# BMS-6S-1B_Sch.net
KiCad netlist of a schematic drawn in Altium Designer
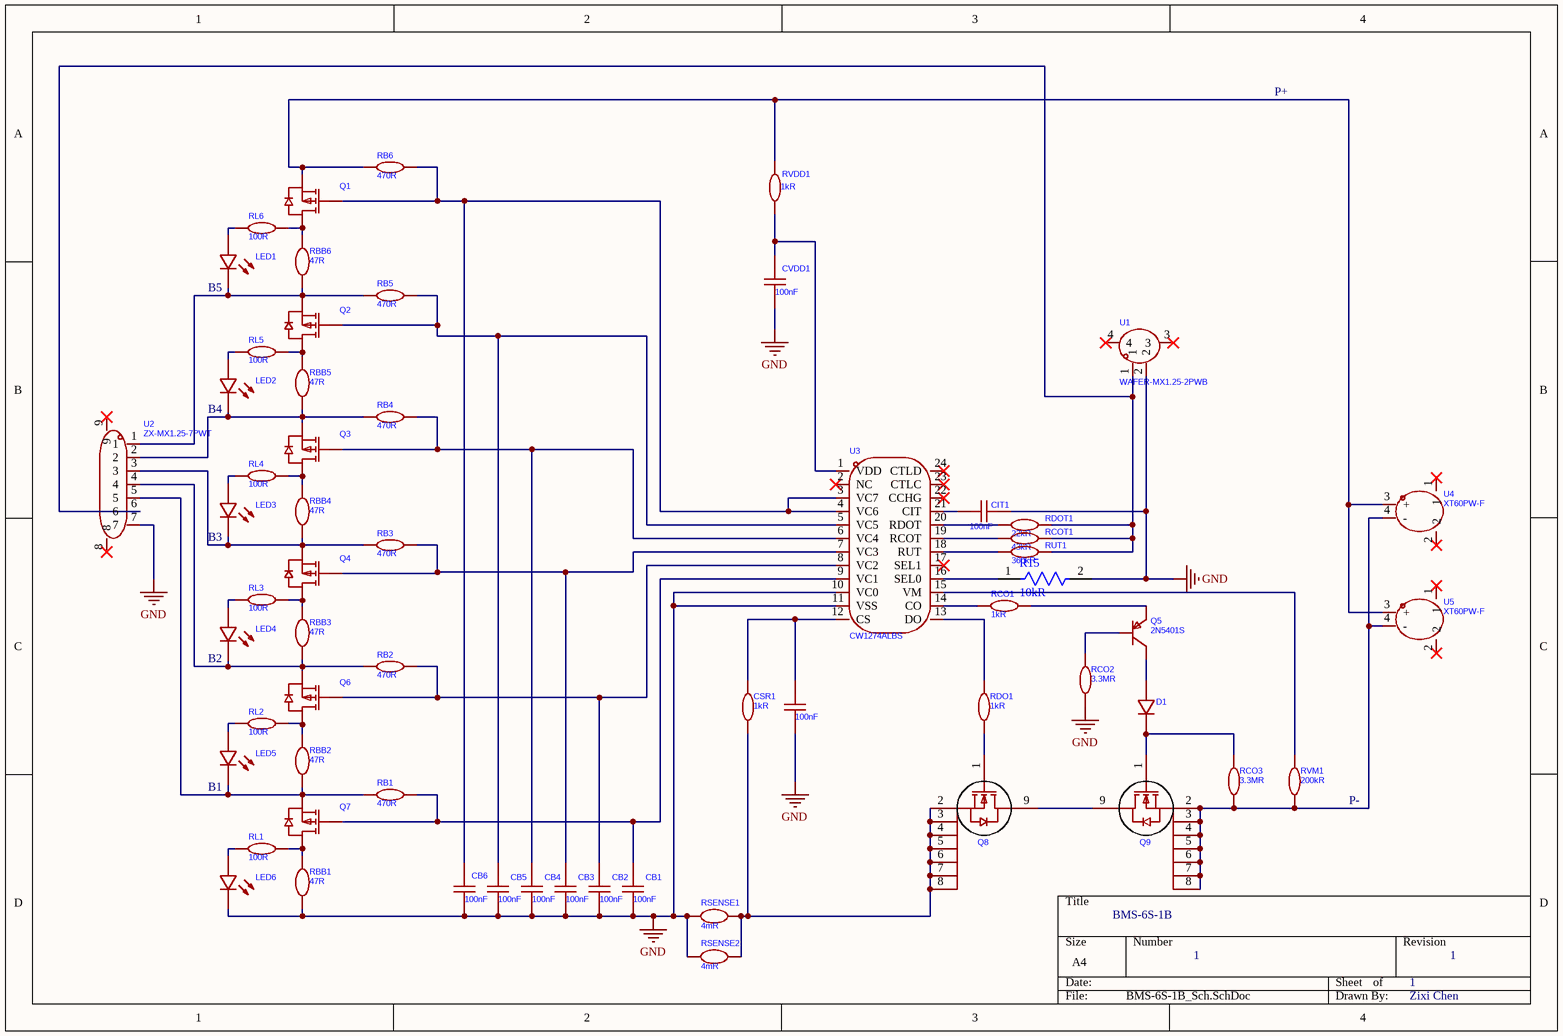
[diagram p0: BMS-6S-1B_Sch.SchDoc]

(export (version "E")
  (design (tool "Eeschema 10.0.6"))
  (components
    (comp (ref "CB1")
      (value "100nF")
      (footprint "C0603")
      (fields
        (field (name "MANUFACTURER") "muRata(村田)")
        (field (name "MANUFACTURER PART") "GCJ188R71H104KA12D")
        (field (name "TOLERANCE") "10%")
      )
      (libsource (lib "Zixi's  personal space") (part "GCJ188R71H104KA12D"))
    )
    (comp (ref "CB2")
      (value "100nF")
      (footprint "C0603")
      (fields
        (field (name "MANUFACTURER") "muRata(村田)")
        (field (name "MANUFACTURER PART") "GCJ188R71H104KA12D")
        (field (name "TOLERANCE") "10%")
      )
      (libsource (lib "Zixi's  personal space") (part "GCJ188R71H104KA12D"))
    )
    (comp (ref "CB3")
      (value "100nF")
      (footprint "C0603")
      (fields
        (field (name "MANUFACTURER") "muRata(村田)")
        (field (name "MANUFACTURER PART") "GCJ188R71H104KA12D")
        (field (name "TOLERANCE") "10%")
      )
      (libsource (lib "Zixi's  personal space") (part "GCJ188R71H104KA12D"))
    )
    (comp (ref "CB4")
      (value "100nF")
      (footprint "C0603")
      (fields
        (field (name "MANUFACTURER") "muRata(村田)")
        (field (name "MANUFACTURER PART") "GCJ188R71H104KA12D")
        (field (name "TOLERANCE") "10%")
      )
      (libsource (lib "Zixi's  personal space") (part "GCJ188R71H104KA12D"))
    )
    (comp (ref "CB5")
      (value "100nF")
      (footprint "C0603")
      (fields
        (field (name "MANUFACTURER") "muRata(村田)")
        (field (name "MANUFACTURER PART") "GCJ188R71H104KA12D")
        (field (name "TOLERANCE") "10%")
      )
      (libsource (lib "Zixi's  personal space") (part "GCJ188R71H104KA12D"))
    )
    (comp (ref "CB6")
      (value "100nF")
      (footprint "C0603")
      (fields
        (field (name "MANUFACTURER") "muRata(村田)")
        (field (name "MANUFACTURER PART") "GCJ188R71H104KA12D")
        (field (name "TOLERANCE") "10%")
      )
      (libsource (lib "Zixi's  personal space") (part "GCJ188R71H104KA12D"))
    )
    (comp (ref "CIT1")
      (value "100nF")
      (footprint "C0603")
      (fields
        (field (name "MANUFACTURER") "muRata(村田)")
        (field (name "MANUFACTURER PART") "GCJ188R71H104KA12D")
        (field (name "TOLERANCE") "10%")
      )
      (libsource (lib "Zixi's  personal space") (part "GCJ188R71H104KA12D"))
    )
    (comp (ref "CSC1")
      (value "100nF")
      (footprint "C0603")
      (fields
        (field (name "MANUFACTURER") "muRata(村田)")
        (field (name "MANUFACTURER PART") "GCJ188R71H104KA12D")
        (field (name "TOLERANCE") "10%")
      )
      (libsource (lib "Zixi's  personal space") (part "GCJ188R71H104KA12D"))
    )
    (comp (ref "CSR1")
      (value "1kR")
      (footprint "R0603")
      (fields
        (field (name "MANUFACTURER") "UNI-ROYAL(厚声)")
        (field (name "TOLERANCE") "1%")
        (field (name "MANUFACTURER PART") "0603WAF1001T5E")
      )
      (libsource (lib "Zixi's  personal space") (part "RC0603FR-07100RL"))
    )
    (comp (ref "CVDD1")
      (value "100nF")
      (footprint "C0603")
      (fields
        (field (name "MANUFACTURER") "muRata(村田)")
        (field (name "MANUFACTURER PART") "GCJ188R71H104KA12D")
        (field (name "TOLERANCE") "10%")
      )
      (libsource (lib "Zixi's  personal space") (part "GCJ188R71H104KA12D"))
    )
    (comp (ref "D1")
      (value "1SS355_C8485")
      (footprint "SOD-323_L1.8-W1.3-LS2.5-RD")
      (fields (field (name "MANUFACTURER") "CJ(江苏长电/长晶)") (field (name "MANUFACTURER PART") "1SS355"))
      (libsource (lib "Zixi's  personal space") (part "1SS355_C8485"))
    )
    (comp (ref "LED1")
      (value "NCD0603O1")
      (footprint "LED0603-RD")
      (fields (field (name "MANUFACTURER") "国星光电"))
      (libsource (lib "Zixi's  personal space") (part "NCD0603O1"))
    )
    (comp (ref "LED2")
      (value "NCD0603O1")
      (footprint "LED0603-RD")
      (fields (field (name "MANUFACTURER") "国星光电"))
      (libsource (lib "Zixi's  personal space") (part "NCD0603O1"))
    )
    (comp (ref "LED3")
      (value "NCD0603O1")
      (footprint "LED0603-RD")
      (fields (field (name "MANUFACTURER") "国星光电"))
      (libsource (lib "Zixi's  personal space") (part "NCD0603O1"))
    )
    (comp (ref "LED4")
      (value "NCD0603O1")
      (footprint "LED0603-RD")
      (fields (field (name "MANUFACTURER") "国星光电"))
      (libsource (lib "Zixi's  personal space") (part "NCD0603O1"))
    )
    (comp (ref "LED5")
      (value "NCD0603O1")
      (footprint "LED0603-RD")
      (fields (field (name "MANUFACTURER") "国星光电"))
      (libsource (lib "Zixi's  personal space") (part "NCD0603O1"))
    )
    (comp (ref "LED6")
      (value "NCD0603O1")
      (footprint "LED0603-RD")
      (fields (field (name "MANUFACTURER") "国星光电"))
      (libsource (lib "Zixi's  personal space") (part "NCD0603O1"))
    )
    (comp (ref "Q1")
      (value "AO3401A_C15127")
      (footprint "SOT-23_L2.9-W1.3-P1.90-LS2.4-BR")
      (fields (field (name "MANUFACTURER PART") "AO3401A") (field (name "MANUFACTURER") "AOS"))
      (libsource (lib "Zixi's  personal space") (part "AO3401A_C15127"))
    )
    (comp (ref "Q2")
      (value "AO3401A_C15127")
      (footprint "SOT-23_L2.9-W1.3-P1.90-LS2.4-BR")
      (fields (field (name "MANUFACTURER PART") "AO3401A") (field (name "MANUFACTURER") "AOS"))
      (libsource (lib "Zixi's  personal space") (part "AO3401A_C15127"))
    )
    (comp (ref "Q3")
      (value "AO3401A_C15127")
      (footprint "SOT-23_L2.9-W1.3-P1.90-LS2.4-BR")
      (fields (field (name "MANUFACTURER PART") "AO3401A") (field (name "MANUFACTURER") "AOS"))
      (libsource (lib "Zixi's  personal space") (part "AO3401A_C15127"))
    )
    (comp (ref "Q4")
      (value "AO3401A_C15127")
      (footprint "SOT-23_L2.9-W1.3-P1.90-LS2.4-BR")
      (fields (field (name "MANUFACTURER PART") "AO3401A") (field (name "MANUFACTURER") "AOS"))
      (libsource (lib "Zixi's  personal space") (part "AO3401A_C15127"))
    )
    (comp (ref "Q5")
      (value "2N5401S")
      (footprint "SOT-23-3_L2.9-W1.5-P2.0-LS2.5-BR")
      (fields (field (name "MANUFACTURER") "TECH PUBLIC(台舟)"))
      (libsource (lib "Zixi's  personal space") (part "2N5401S"))
    )
    (comp (ref "Q6")
      (value "AO3401A_C15127")
      (footprint "SOT-23_L2.9-W1.3-P1.90-LS2.4-BR")
      (fields (field (name "MANUFACTURER PART") "AO3401A") (field (name "MANUFACTURER") "AOS"))
      (libsource (lib "Zixi's  personal space") (part "AO3401A_C15127"))
    )
    (comp (ref "Q7")
      (value "AO3401A_C15127")
      (footprint "SOT-23_L2.9-W1.3-P1.90-LS2.4-BR")
      (fields (field (name "MANUFACTURER PART") "AO3401A") (field (name "MANUFACTURER") "AOS"))
      (libsource (lib "Zixi's  personal space") (part "AO3401A_C15127"))
    )
    (comp (ref "Q8")
      (value "IPLU250N04S4-1R7")
      (footprint "PG-HSOF-8_L10.5-W10.1-P1.20-LS11.9-TL")
      (fields (field (name "MANUFACTURER") "Infineon(英飞凌)"))
      (libsource (lib "Zixi's  personal space") (part "IPLU250N04S4-1R7"))
    )
    (comp (ref "Q9")
      (value "IPLU250N04S4-1R7")
      (footprint "PG-HSOF-8_L10.5-W10.1-P1.20-LS11.9-TL")
      (fields (field (name "MANUFACTURER") "Infineon(英飞凌)"))
      (libsource (lib "Zixi's  personal space") (part "IPLU250N04S4-1R7"))
    )
    (comp (ref "R15")
      (value "10kR")
      (footprint "FP-ESR10-IPC_C")
      (description "10kΩ ±0.5% 0.4W 0805 Anti-Surge Chip Resistor AEC-Q200")
      (libsource (lib "Altium Content Vault") (part "1029c3af85768c4190bb7ad29bc67b5"))
    )
    (comp (ref "RB1")
      (value "470R")
      (footprint "R0603")
      (fields
        (field (name "MANUFACTURER") "UNI-ROYAL(厚声)")
        (field (name "MANUFACTURER PART") "0603WAF4700T5E")
        (field (name "TOLERANCE") "1%")
      )
      (libsource (lib "Zixi's  personal space") (part "RC0603FR-07100RL"))
    )
    (comp (ref "RB2")
      (value "470R")
      (footprint "R0603")
      (fields
        (field (name "MANUFACTURER") "UNI-ROYAL(厚声)")
        (field (name "MANUFACTURER PART") "0603WAF4700T5E")
        (field (name "TOLERANCE") "1%")
      )
      (libsource (lib "Zixi's  personal space") (part "RC0603FR-07100RL"))
    )
    (comp (ref "RB3")
      (value "470R")
      (footprint "R0603")
      (fields
        (field (name "MANUFACTURER") "UNI-ROYAL(厚声)")
        (field (name "MANUFACTURER PART") "0603WAF4700T5E")
        (field (name "TOLERANCE") "1%")
      )
      (libsource (lib "Zixi's  personal space") (part "RC0603FR-07100RL"))
    )
    (comp (ref "RB4")
      (value "470R")
      (footprint "R0603")
      (fields
        (field (name "MANUFACTURER") "UNI-ROYAL(厚声)")
        (field (name "MANUFACTURER PART") "0603WAF4700T5E")
        (field (name "TOLERANCE") "1%")
      )
      (libsource (lib "Zixi's  personal space") (part "RC0603FR-07100RL"))
    )
    (comp (ref "RB5")
      (value "470R")
      (footprint "R0603")
      (fields
        (field (name "MANUFACTURER") "UNI-ROYAL(厚声)")
        (field (name "MANUFACTURER PART") "0603WAF4700T5E")
        (field (name "TOLERANCE") "1%")
      )
      (libsource (lib "Zixi's  personal space") (part "RC0603FR-07100RL"))
    )
    (comp (ref "RB6")
      (value "470R")
      (footprint "R0603")
      (fields
        (field (name "MANUFACTURER") "UNI-ROYAL(厚声)")
        (field (name "MANUFACTURER PART") "0603WAF4700T5E")
        (field (name "TOLERANCE") "1%")
      )
      (libsource (lib "Zixi's  personal space") (part "RC0603FR-07100RL"))
    )
    (comp (ref "RBB1")
      (value "47R")
      (footprint "R2512")
      (fields
        (field (name "TOLERANCE") "1%")
        (field (name "MANUFACTURER") "FH(风华)")
        (field (name "MANUFACTURER PART") "RC-12K47R0FT")
      )
      (libsource (lib "Zixi's  personal space") (part "HolRS3920-3W-4mR-1"))
    )
    (comp (ref "RBB2")
      (value "47R")
      (footprint "R2512")
      (fields
        (field (name "TOLERANCE") "1%")
        (field (name "MANUFACTURER") "FH(风华)")
        (field (name "MANUFACTURER PART") "RC-12K47R0FT")
      )
      (libsource (lib "Zixi's  personal space") (part "HolRS3920-3W-4mR-1"))
    )
    (comp (ref "RBB3")
      (value "47R")
      (footprint "R2512")
      (fields
        (field (name "TOLERANCE") "1%")
        (field (name "MANUFACTURER") "FH(风华)")
        (field (name "MANUFACTURER PART") "RC-12K47R0FT")
      )
      (libsource (lib "Zixi's  personal space") (part "HolRS3920-3W-4mR-1"))
    )
    (comp (ref "RBB4")
      (value "47R")
      (footprint "R2512")
      (fields
        (field (name "TOLERANCE") "1%")
        (field (name "MANUFACTURER") "FH(风华)")
        (field (name "MANUFACTURER PART") "RC-12K47R0FT")
      )
      (libsource (lib "Zixi's  personal space") (part "HolRS3920-3W-4mR-1"))
    )
    (comp (ref "RBB5")
      (value "47R")
      (footprint "R2512")
      (fields
        (field (name "TOLERANCE") "1%")
        (field (name "MANUFACTURER") "FH(风华)")
        (field (name "MANUFACTURER PART") "RC-12K47R0FT")
      )
      (libsource (lib "Zixi's  personal space") (part "HolRS3920-3W-4mR-1"))
    )
    (comp (ref "RBB6")
      (value "47R")
      (footprint "R2512")
      (fields
        (field (name "TOLERANCE") "1%")
        (field (name "MANUFACTURER") "FH(风华)")
        (field (name "MANUFACTURER PART") "RC-12K47R0FT")
      )
      (libsource (lib "Zixi's  personal space") (part "HolRS3920-3W-4mR-1"))
    )
    (comp (ref "RCO1")
      (value "1kR")
      (footprint "R0603")
      (fields
        (field (name "MANUFACTURER PART") "0603WAF1001T5E")
        (field (name "MANUFACTURER") "UNI-ROYAL(厚声)")
        (field (name "TOLERANCE") "1%")
      )
      (libsource (lib "Zixi's  personal space") (part "RC0603FR-07100RL"))
    )
    (comp (ref "RCO2")
      (value "3.3MR")
      (footprint "R0603")
      (fields
        (field (name "MANUFACTURER PART") "0603WAF3304T5E")
        (field (name "MANUFACTURER") "UNI-ROYAL(厚声)")
        (field (name "TOLERANCE") "1%")
      )
      (libsource (lib "Zixi's  personal space") (part "RC0603FR-07100RL"))
    )
    (comp (ref "RCO3")
      (value "3.3MR")
      (footprint "R0603")
      (fields
        (field (name "MANUFACTURER PART") "0603WAF3304T5E")
        (field (name "MANUFACTURER") "UNI-ROYAL(厚声)")
        (field (name "TOLERANCE") "1%")
      )
      (libsource (lib "Zixi's  personal space") (part "RC0603FR-07100RL"))
    )
    (comp (ref "RCOT1")
      (value "43kR")
      (footprint "R0603")
      (fields
        (field (name "MANUFACTURER") "UNI-ROYAL(厚声)")
        (field (name "TOLERANCE") "1%")
        (field (name "MANUFACTURER PART") "0603WAF4302T5E")
      )
      (libsource (lib "Zixi's  personal space") (part "RC0603FR-07100RL"))
    )
    (comp (ref "RDO1")
      (value "1kR")
      (footprint "R0603")
      (fields
        (field (name "MANUFACTURER PART") "0603WAF1001T5E")
        (field (name "MANUFACTURER") "UNI-ROYAL(厚声)")
        (field (name "TOLERANCE") "1%")
      )
      (libsource (lib "Zixi's  personal space") (part "RC0603FR-07100RL"))
    )
    (comp (ref "RDOT1")
      (value "22kR")
      (footprint "R0603")
      (fields
        (field (name "TOLERANCE") "1%")
        (field (name "MANUFACTURER PART") "0603WAF2202T5E")
        (field (name "MANUFACTURER") "UNI-ROYAL(厚声)")
      )
      (libsource (lib "Zixi's  personal space") (part "RC0603FR-07100RL"))
    )
    (comp (ref "RL1")
      (value "100R")
      (footprint "R0603")
      (fields
        (field (name "MANUFACTURER PART") "RC0603FR-07100RL")
        (field (name "TOLERANCE") "1%")
        (field (name "MANUFACTURER") "YAGEO(国巨)")
      )
      (libsource (lib "Zixi's  personal space") (part "RC0603FR-07100RL"))
    )
    (comp (ref "RL2")
      (value "100R")
      (footprint "R0603")
      (fields
        (field (name "MANUFACTURER PART") "RC0603FR-07100RL")
        (field (name "TOLERANCE") "1%")
        (field (name "MANUFACTURER") "YAGEO(国巨)")
      )
      (libsource (lib "Zixi's  personal space") (part "RC0603FR-07100RL"))
    )
    (comp (ref "RL3")
      (value "100R")
      (footprint "R0603")
      (fields
        (field (name "MANUFACTURER PART") "RC0603FR-07100RL")
        (field (name "TOLERANCE") "1%")
        (field (name "MANUFACTURER") "YAGEO(国巨)")
      )
      (libsource (lib "Zixi's  personal space") (part "RC0603FR-07100RL"))
    )
    (comp (ref "RL4")
      (value "100R")
      (footprint "R0603")
      (fields
        (field (name "MANUFACTURER PART") "RC0603FR-07100RL")
        (field (name "TOLERANCE") "1%")
        (field (name "MANUFACTURER") "YAGEO(国巨)")
      )
      (libsource (lib "Zixi's  personal space") (part "RC0603FR-07100RL"))
    )
    (comp (ref "RL5")
      (value "100R")
      (footprint "R0603")
      (fields
        (field (name "MANUFACTURER PART") "RC0603FR-07100RL")
        (field (name "TOLERANCE") "1%")
        (field (name "MANUFACTURER") "YAGEO(国巨)")
      )
      (libsource (lib "Zixi's  personal space") (part "RC0603FR-07100RL"))
    )
    (comp (ref "RL6")
      (value "100R")
      (footprint "R0603")
      (fields
        (field (name "MANUFACTURER PART") "RC0603FR-07100RL")
        (field (name "TOLERANCE") "1%")
        (field (name "MANUFACTURER") "YAGEO(国巨)")
      )
      (libsource (lib "Zixi's  personal space") (part "RC0603FR-07100RL"))
    )
    (comp (ref "RSENSE1")
      (value "4mR")
      (footprint "R3920")
      (fields
        (field (name "MANUFACTURER PART") "HolRS3920-3W-4mR-1%")
        (field (name "MANUFACTURER") "Milliohm(毫欧)")
        (field (name "TOLERANCE") "1%")
      )
      (libsource (lib "Zixi's  personal space") (part "HolRS3920-3W-4mR-1"))
    )
    (comp (ref "RSENSE2")
      (value "4mR")
      (footprint "R3920")
      (fields
        (field (name "MANUFACTURER PART") "HolRS3920-3W-4mR-1%")
        (field (name "MANUFACTURER") "Milliohm(毫欧)")
        (field (name "TOLERANCE") "1%")
      )
      (libsource (lib "Zixi's  personal space") (part "HolRS3920-3W-4mR-1"))
    )
    (comp (ref "RUT1")
      (value "360kR")
      (footprint "R0603")
      (fields
        (field (name "MANUFACTURER PART") "0603WAF3603T5E")
        (field (name "TOLERANCE") "1%")
        (field (name "MANUFACTURER") "UNI-ROYAL(厚声)")
      )
      (libsource (lib "Zixi's  personal space") (part "RC0603FR-07100RL"))
    )
    (comp (ref "RVDD1")
      (value "1kR")
      (footprint "R0603")
      (fields
        (field (name "MANUFACTURER") "UNI-ROYAL(厚声)")
        (field (name "TOLERANCE") "1%")
        (field (name "MANUFACTURER PART") "0603WAF1001T5E")
      )
      (libsource (lib "Zixi's  personal space") (part "RC0603FR-07100RL"))
    )
    (comp (ref "RVM1")
      (value "200kR")
      (footprint "R0603")
      (fields
        (field (name "MANUFACTURER PART") "0603WAF2003T5E")
        (field (name "MANUFACTURER") "UNI-ROYAL(厚声)")
        (field (name "TOLERANCE") "1%")
      )
      (libsource (lib "Zixi's  personal space") (part "RC0603FR-07100RL"))
    )
    (comp (ref "U1")
      (value "WAFER-MX1.25-2PWB")
      (footprint "CONN-SMD_2P-P1.25_XUNPU_WAFER-MX1.25-2PWB")
      (fields (field (name "MANUFACTURER") "XUNPU(讯普)"))
      (libsource (lib "Zixi's  personal space") (part "WAFER-MX1.25-2PWB"))
    )
    (comp (ref "U2")
      (value "ZX-MX1.25-7PWT")
      (footprint "CONN-SMD_7P-P1.25_ZX-MX1.25-7PWT")
      (fields (field (name "MANUFACTURER") "Megastar(兆星)"))
      (libsource (lib "Zixi's  personal space") (part "ZX-MX1.25-7PWT"))
    )
    (comp (ref "U3")
      (value "CW1274ALBS")
      (footprint "SSOP-24_L8.7-W3.9-P0.64-LS6.0-BL")
      (libsource (lib "Zixi's  personal space") (part "CW1274ALBS"))
    )
    (comp (ref "U4")
      (value "XT60PW-F")
      (footprint "TH_2P-XT60PW-F")
      (fields (field (name "MANUFACTURER") "AMASS(艾迈斯)"))
      (libsource (lib "Zixi's  personal space") (part "XT60PW-F"))
    )
    (comp (ref "U5")
      (value "XT60PW-F")
      (footprint "TH_2P-XT60PW-F")
      (fields (field (name "MANUFACTURER") "AMASS(艾迈斯)"))
      (libsource (lib "Zixi's  personal space") (part "XT60PW-F"))
    )
  )
  (nets
    (net (code "1") (name "GND") (class "Default")
      (node (ref "CB1") (pin "1") (pinfunction "1_1") (pintype "passive"))
      (node (ref "CB2") (pin "1") (pinfunction "1_1") (pintype "passive"))
      (node (ref "CB3") (pin "1") (pinfunction "1_1") (pintype "passive"))
      (node (ref "CB4") (pin "1") (pinfunction "1_1") (pintype "passive"))
      (node (ref "CB5") (pin "1") (pinfunction "1_1") (pintype "passive"))
      (node (ref "CB6") (pin "1") (pinfunction "1_1") (pintype "passive"))
      (node (ref "CIT1") (pin "1") (pinfunction "1_1") (pintype "passive"))
      (node (ref "CSC1") (pin "1") (pinfunction "1_1") (pintype "passive"))
      (node (ref "CVDD1") (pin "1") (pinfunction "1_1") (pintype "passive"))
      (node (ref "LED6") (pin "1") (pinfunction "K_1") (pintype "passive"))
      (node (ref "R15") (pin "2") (pinfunction "2_2") (pintype "passive"))
      (node (ref "RBB1") (pin "1") (pinfunction "1_1") (pintype "passive"))
      (node (ref "RCO2") (pin "1") (pinfunction "1_1") (pintype "passive"))
      (node (ref "RSENSE1") (pin "1") (pinfunction "1_1") (pintype "passive"))
      (node (ref "RSENSE2") (pin "1") (pinfunction "1_1") (pintype "passive"))
      (node (ref "U1") (pin "2") (pinfunction "2_2") (pintype "passive"))
      (node (ref "U2") (pin "7") (pinfunction "7_7") (pintype "passive"))
      (node (ref "U3") (pin "10") (pinfunction "VC0_10") (pintype "passive"))
      (node (ref "U3") (pin "11") (pinfunction "VSS_11") (pintype "passive"))
    )
    (net (code "2") (name "Net-(CSR1-Pad1)") (class "Default")
      (node (ref "CSR1") (pin "1") (pinfunction "1_1") (pintype "passive"))
      (node (ref "Q8") (pin "2") (pinfunction "S_2") (pintype "passive"))
      (node (ref "Q8") (pin "3") (pinfunction "S_3") (pintype "passive"))
      (node (ref "Q8") (pin "4") (pinfunction "S_4") (pintype "passive"))
      (node (ref "Q8") (pin "5") (pinfunction "S_5") (pintype "passive"))
      (node (ref "Q8") (pin "6") (pinfunction "S_6") (pintype "passive"))
      (node (ref "Q8") (pin "7") (pinfunction "S_7") (pintype "passive"))
      (node (ref "Q8") (pin "8") (pinfunction "S_8") (pintype "passive"))
      (node (ref "RSENSE1") (pin "2") (pinfunction "2_2") (pintype "passive"))
      (node (ref "RSENSE2") (pin "2") (pinfunction "2_2") (pintype "passive"))
    )
    (net (code "3") (name "Net-(D1-A)") (class "Default")
      (node (ref "D1") (pin "2") (pinfunction "A_2") (pintype "passive"))
      (node (ref "Q5") (pin "3") (pinfunction "C_3") (pintype "passive"))
    )
    (net (code "4") (name "Net-(D1-K)") (class "Default")
      (node (ref "D1") (pin "1") (pinfunction "K_1") (pintype "passive"))
      (node (ref "Q9") (pin "1") (pinfunction "G_1") (pintype "passive"))
      (node (ref "RCO3") (pin "2") (pinfunction "2_2") (pintype "passive"))
    )
    (net (code "5") (name "Net-(LED1-A)") (class "Default")
      (node (ref "LED1") (pin "2") (pinfunction "A_2") (pintype "passive"))
      (node (ref "RL6") (pin "1") (pinfunction "1_1") (pintype "passive"))
    )
    (net (code "6") (name "Net-(LED1-K)") (class "Default")
      (node (ref "LED1") (pin "1") (pinfunction "K_1") (pintype "passive"))
      (node (ref "Q2") (pin "2") (pinfunction "S_2") (pintype "passive"))
      (node (ref "RB5") (pin "1") (pinfunction "1_1") (pintype "passive"))
      (node (ref "RBB6") (pin "1") (pinfunction "1_1") (pintype "passive"))
      (node (ref "U2") (pin "1") (pinfunction "1_1") (pintype "passive"))
    )
    (net (code "7") (name "Net-(LED2-A)") (class "Default")
      (node (ref "LED2") (pin "2") (pinfunction "A_2") (pintype "passive"))
      (node (ref "RL5") (pin "1") (pinfunction "1_1") (pintype "passive"))
    )
    (net (code "8") (name "Net-(LED2-K)") (class "Default")
      (node (ref "LED2") (pin "1") (pinfunction "K_1") (pintype "passive"))
      (node (ref "Q3") (pin "2") (pinfunction "S_2") (pintype "passive"))
      (node (ref "RB4") (pin "1") (pinfunction "1_1") (pintype "passive"))
      (node (ref "RBB5") (pin "1") (pinfunction "1_1") (pintype "passive"))
      (node (ref "U2") (pin "2") (pinfunction "2_2") (pintype "passive"))
    )
    (net (code "9") (name "Net-(LED3-A)") (class "Default")
      (node (ref "LED3") (pin "2") (pinfunction "A_2") (pintype "passive"))
      (node (ref "RL4") (pin "1") (pinfunction "1_1") (pintype "passive"))
    )
    (net (code "10") (name "Net-(LED3-K)") (class "Default")
      (node (ref "LED3") (pin "1") (pinfunction "K_1") (pintype "passive"))
      (node (ref "Q4") (pin "2") (pinfunction "S_2") (pintype "passive"))
      (node (ref "RB3") (pin "1") (pinfunction "1_1") (pintype "passive"))
      (node (ref "RBB4") (pin "1") (pinfunction "1_1") (pintype "passive"))
      (node (ref "U2") (pin "3") (pinfunction "3_3") (pintype "passive"))
    )
    (net (code "11") (name "Net-(LED4-A)") (class "Default")
      (node (ref "LED4") (pin "2") (pinfunction "A_2") (pintype "passive"))
      (node (ref "RL3") (pin "1") (pinfunction "1_1") (pintype "passive"))
    )
    (net (code "12") (name "Net-(LED4-K)") (class "Default")
      (node (ref "LED4") (pin "1") (pinfunction "K_1") (pintype "passive"))
      (node (ref "Q6") (pin "2") (pinfunction "S_2") (pintype "passive"))
      (node (ref "RB2") (pin "1") (pinfunction "1_1") (pintype "passive"))
      (node (ref "RBB3") (pin "1") (pinfunction "1_1") (pintype "passive"))
      (node (ref "U2") (pin "4") (pinfunction "4_4") (pintype "passive"))
    )
    (net (code "13") (name "Net-(LED5-A)") (class "Default")
      (node (ref "LED5") (pin "2") (pinfunction "A_2") (pintype "passive"))
      (node (ref "RL2") (pin "1") (pinfunction "1_1") (pintype "passive"))
    )
    (net (code "14") (name "Net-(LED5-K)") (class "Default")
      (node (ref "LED5") (pin "1") (pinfunction "K_1") (pintype "passive"))
      (node (ref "Q7") (pin "2") (pinfunction "S_2") (pintype "passive"))
      (node (ref "RB1") (pin "1") (pinfunction "1_1") (pintype "passive"))
      (node (ref "RBB2") (pin "1") (pinfunction "1_1") (pintype "passive"))
      (node (ref "U2") (pin "5") (pinfunction "5_5") (pintype "passive"))
    )
    (net (code "15") (name "Net-(LED6-A)") (class "Default")
      (node (ref "LED6") (pin "2") (pinfunction "A_2") (pintype "passive"))
      (node (ref "RL1") (pin "1") (pinfunction "1_1") (pintype "passive"))
    )
    (net (code "16") (name "Net-(Q1-D)") (class "Default")
      (node (ref "Q1") (pin "3") (pinfunction "D_3") (pintype "passive"))
      (node (ref "RBB6") (pin "2") (pinfunction "2_2") (pintype "passive"))
      (node (ref "RL6") (pin "2") (pinfunction "2_2") (pintype "passive"))
    )
    (net (code "17") (name "Net-(Q1-G)") (class "Default")
      (node (ref "CB6") (pin "2") (pinfunction "2_2") (pintype "passive"))
      (node (ref "Q1") (pin "1") (pinfunction "G_1") (pintype "passive"))
      (node (ref "RB6") (pin "2") (pinfunction "2_2") (pintype "passive"))
      (node (ref "U3") (pin "3") (pinfunction "VC7_3") (pintype "passive"))
      (node (ref "U3") (pin "4") (pinfunction "VC6_4") (pintype "passive"))
    )
    (net (code "18") (name "Net-(Q1-S)") (class "Default")
      (node (ref "Q1") (pin "2") (pinfunction "S_2") (pintype "passive"))
      (node (ref "RB6") (pin "1") (pinfunction "1_1") (pintype "passive"))
      (node (ref "RVDD1") (pin "2") (pinfunction "2_2") (pintype "passive"))
      (node (ref "U4") (pin "3") (pinfunction "+_3") (pintype "passive"))
      (node (ref "U5") (pin "3") (pinfunction "+_3") (pintype "passive"))
    )
    (net (code "19") (name "Net-(Q2-D)") (class "Default")
      (node (ref "Q2") (pin "3") (pinfunction "D_3") (pintype "passive"))
      (node (ref "RBB5") (pin "2") (pinfunction "2_2") (pintype "passive"))
      (node (ref "RL5") (pin "2") (pinfunction "2_2") (pintype "passive"))
    )
    (net (code "20") (name "Net-(Q2-G)") (class "Default")
      (node (ref "CB5") (pin "2") (pinfunction "2_2") (pintype "passive"))
      (node (ref "Q2") (pin "1") (pinfunction "G_1") (pintype "passive"))
      (node (ref "RB5") (pin "2") (pinfunction "2_2") (pintype "passive"))
      (node (ref "U3") (pin "5") (pinfunction "VC5_5") (pintype "passive"))
    )
    (net (code "21") (name "Net-(Q3-D)") (class "Default")
      (node (ref "Q3") (pin "3") (pinfunction "D_3") (pintype "passive"))
      (node (ref "RBB4") (pin "2") (pinfunction "2_2") (pintype "passive"))
      (node (ref "RL4") (pin "2") (pinfunction "2_2") (pintype "passive"))
    )
    (net (code "22") (name "Net-(Q3-G)") (class "Default")
      (node (ref "CB4") (pin "2") (pinfunction "2_2") (pintype "passive"))
      (node (ref "Q3") (pin "1") (pinfunction "G_1") (pintype "passive"))
      (node (ref "RB4") (pin "2") (pinfunction "2_2") (pintype "passive"))
      (node (ref "U3") (pin "6") (pinfunction "VC4_6") (pintype "passive"))
    )
    (net (code "23") (name "Net-(Q4-D)") (class "Default")
      (node (ref "Q4") (pin "3") (pinfunction "D_3") (pintype "passive"))
      (node (ref "RBB3") (pin "2") (pinfunction "2_2") (pintype "passive"))
      (node (ref "RL3") (pin "2") (pinfunction "2_2") (pintype "passive"))
    )
    (net (code "24") (name "Net-(Q4-G)") (class "Default")
      (node (ref "CB3") (pin "2") (pinfunction "2_2") (pintype "passive"))
      (node (ref "Q4") (pin "1") (pinfunction "G_1") (pintype "passive"))
      (node (ref "RB3") (pin "2") (pinfunction "2_2") (pintype "passive"))
      (node (ref "U3") (pin "7") (pinfunction "VC3_7") (pintype "passive"))
    )
    (net (code "25") (name "Net-(Q5-B)") (class "Default")
      (node (ref "Q5") (pin "1") (pinfunction "B_1") (pintype "passive"))
      (node (ref "RCO2") (pin "2") (pinfunction "2_2") (pintype "passive"))
    )
    (net (code "26") (name "Net-(Q5-E)") (class "Default")
      (node (ref "Q5") (pin "2") (pinfunction "E_2") (pintype "passive"))
      (node (ref "RCO1") (pin "2") (pinfunction "2_2") (pintype "passive"))
    )
    (net (code "27") (name "Net-(Q6-D)") (class "Default")
      (node (ref "Q6") (pin "3") (pinfunction "D_3") (pintype "passive"))
      (node (ref "RBB2") (pin "2") (pinfunction "2_2") (pintype "passive"))
      (node (ref "RL2") (pin "2") (pinfunction "2_2") (pintype "passive"))
    )
    (net (code "28") (name "Net-(Q6-G)") (class "Default")
      (node (ref "CB2") (pin "2") (pinfunction "2_2") (pintype "passive"))
      (node (ref "Q6") (pin "1") (pinfunction "G_1") (pintype "passive"))
      (node (ref "RB2") (pin "2") (pinfunction "2_2") (pintype "passive"))
      (node (ref "U3") (pin "8") (pinfunction "VC2_8") (pintype "passive"))
    )
    (net (code "29") (name "Net-(Q7-D)") (class "Default")
      (node (ref "Q7") (pin "3") (pinfunction "D_3") (pintype "passive"))
      (node (ref "RBB1") (pin "2") (pinfunction "2_2") (pintype "passive"))
      (node (ref "RL1") (pin "2") (pinfunction "2_2") (pintype "passive"))
    )
    (net (code "30") (name "Net-(Q7-G)") (class "Default")
      (node (ref "CB1") (pin "2") (pinfunction "2_2") (pintype "passive"))
      (node (ref "Q7") (pin "1") (pinfunction "G_1") (pintype "passive"))
      (node (ref "RB1") (pin "2") (pinfunction "2_2") (pintype "passive"))
      (node (ref "U3") (pin "9") (pinfunction "VC1_9") (pintype "passive"))
    )
    (net (code "31") (name "Net-(Q8-D)") (class "Default")
      (node (ref "Q8") (pin "9") (pinfunction "D_9") (pintype "passive"))
      (node (ref "Q9") (pin "9") (pinfunction "D_9") (pintype "passive"))
    )
    (net (code "32") (name "Net-(Q8-G)") (class "Default")
      (node (ref "Q8") (pin "1") (pinfunction "G_1") (pintype "passive"))
      (node (ref "RDO1") (pin "1") (pinfunction "1_1") (pintype "passive"))
    )
    (net (code "33") (name "Net-(RCOT1-Pad2)") (class "Default")
      (node (ref "RCOT1") (pin "2") (pinfunction "2_2") (pintype "passive"))
      (node (ref "RDOT1") (pin "2") (pinfunction "2_2") (pintype "passive"))
      (node (ref "RUT1") (pin "2") (pinfunction "2_2") (pintype "passive"))
      (node (ref "U1") (pin "1") (pinfunction "1_1") (pintype "passive"))
      (node (ref "U2") (pin "6") (pinfunction "6_6") (pintype "passive"))
    )
    (net (code "34") (name "Net-(U3-CIT)") (class "Default")
      (node (ref "CIT1") (pin "2") (pinfunction "2_2") (pintype "passive"))
      (node (ref "U3") (pin "21") (pinfunction "CIT_21") (pintype "passive"))
    )
    (net (code "35") (name "Net-(U3-CO)") (class "Default")
      (node (ref "RCO1") (pin "1") (pinfunction "1_1") (pintype "passive"))
      (node (ref "U3") (pin "14") (pinfunction "CO_14") (pintype "passive"))
    )
    (net (code "36") (name "Net-(U3-CS)") (class "Default")
      (node (ref "CSC1") (pin "2") (pinfunction "2_2") (pintype "passive"))
      (node (ref "CSR1") (pin "2") (pinfunction "2_2") (pintype "passive"))
      (node (ref "U3") (pin "12") (pinfunction "CS_12") (pintype "passive"))
    )
    (net (code "37") (name "Net-(U3-DO)") (class "Default")
      (node (ref "RDO1") (pin "2") (pinfunction "2_2") (pintype "passive"))
      (node (ref "U3") (pin "13") (pinfunction "DO_13") (pintype "passive"))
    )
    (net (code "38") (name "Net-(U3-RCOT)") (class "Default")
      (node (ref "RCOT1") (pin "1") (pinfunction "1_1") (pintype "passive"))
      (node (ref "U3") (pin "19") (pinfunction "RCOT_19") (pintype "passive"))
    )
    (net (code "39") (name "Net-(U3-RDOT)") (class "Default")
      (node (ref "RDOT1") (pin "1") (pinfunction "1_1") (pintype "passive"))
      (node (ref "U3") (pin "20") (pinfunction "RDOT_20") (pintype "passive"))
    )
    (net (code "40") (name "Net-(U3-RUT)") (class "Default")
      (node (ref "RUT1") (pin "1") (pinfunction "1_1") (pintype "passive"))
      (node (ref "U3") (pin "18") (pinfunction "RUT_18") (pintype "passive"))
    )
    (net (code "41") (name "Net-(U3-SEL0)") (class "Default")
      (node (ref "R15") (pin "1") (pinfunction "1_1") (pintype "passive"))
      (node (ref "U3") (pin "16") (pinfunction "SEL0_16") (pintype "passive"))
    )
    (net (code "42") (name "Net-(U3-VDD)") (class "Default")
      (node (ref "CVDD1") (pin "2") (pinfunction "2_2") (pintype "passive"))
      (node (ref "RVDD1") (pin "1") (pinfunction "1_1") (pintype "passive"))
      (node (ref "U3") (pin "1") (pinfunction "VDD_1") (pintype "passive"))
    )
    (net (code "43") (name "Net-(U3-VM)") (class "Default")
      (node (ref "RVM1") (pin "2") (pinfunction "2_2") (pintype "passive"))
      (node (ref "U3") (pin "15") (pinfunction "VM_15") (pintype "passive"))
    )
    (net (code "44") (name "Net-(U4--)") (class "Default")
      (node (ref "Q9") (pin "2") (pinfunction "S_2") (pintype "passive"))
      (node (ref "Q9") (pin "3") (pinfunction "S_3") (pintype "passive"))
      (node (ref "Q9") (pin "4") (pinfunction "S_4") (pintype "passive"))
      (node (ref "Q9") (pin "5") (pinfunction "S_5") (pintype "passive"))
      (node (ref "Q9") (pin "6") (pinfunction "S_6") (pintype "passive"))
      (node (ref "Q9") (pin "7") (pinfunction "S_7") (pintype "passive"))
      (node (ref "Q9") (pin "8") (pinfunction "S_8") (pintype "passive"))
      (node (ref "RCO3") (pin "1") (pinfunction "1_1") (pintype "passive"))
      (node (ref "RVM1") (pin "1") (pinfunction "1_1") (pintype "passive"))
      (node (ref "U4") (pin "4") (pinfunction "-_4") (pintype "passive"))
      (node (ref "U5") (pin "4") (pinfunction "-_4") (pintype "passive"))
    )
    (net (code "45") (name "unconnected-(U1-Pad3)") (class "Default")
      (node (ref "U1") (pin "3") (pinfunction "3_3") (pintype "passive+no_connect"))
    )
    (net (code "46") (name "unconnected-(U1-Pad4)") (class "Default")
      (node (ref "U1") (pin "4") (pinfunction "4_4") (pintype "passive+no_connect"))
    )
    (net (code "47") (name "unconnected-(U2-Pad8)") (class "Default")
      (node (ref "U2") (pin "8") (pinfunction "8_8") (pintype "passive+no_connect"))
    )
    (net (code "48") (name "unconnected-(U2-Pad9)") (class "Default")
      (node (ref "U2") (pin "9") (pinfunction "9_9") (pintype "passive+no_connect"))
    )
    (net (code "49") (name "unconnected-(U3-CCHG-Pad22)") (class "Default")
      (node (ref "U3") (pin "22") (pinfunction "CCHG_22") (pintype "passive+no_connect"))
    )
    (net (code "50") (name "unconnected-(U3-CTLC-Pad23)") (class "Default")
      (node (ref "U3") (pin "23") (pinfunction "CTLC_23") (pintype "passive+no_connect"))
    )
    (net (code "51") (name "unconnected-(U3-CTLD-Pad24)") (class "Default")
      (node (ref "U3") (pin "24") (pinfunction "CTLD_24") (pintype "passive+no_connect"))
    )
    (net (code "52") (name "unconnected-(U3-NC-Pad2)") (class "Default")
      (node (ref "U3") (pin "2") (pinfunction "NC_2") (pintype "passive+no_connect"))
    )
    (net (code "53") (name "unconnected-(U3-SEL1-Pad17)") (class "Default")
      (node (ref "U3") (pin "17") (pinfunction "SEL1_17") (pintype "passive+no_connect"))
    )
    (net (code "54") (name "unconnected-(U4-Pad1)") (class "Default")
      (node (ref "U4") (pin "1") (pinfunction "1_1") (pintype "passive+no_connect"))
    )
    (net (code "55") (name "unconnected-(U4-Pad2)") (class "Default")
      (node (ref "U4") (pin "2") (pinfunction "2_2") (pintype "passive+no_connect"))
    )
    (net (code "56") (name "unconnected-(U5-Pad1)") (class "Default")
      (node (ref "U5") (pin "1") (pinfunction "1_1") (pintype "passive+no_connect"))
    )
    (net (code "57") (name "unconnected-(U5-Pad2)") (class "Default")
      (node (ref "U5") (pin "2") (pinfunction "2_2") (pintype "passive+no_connect"))
    )
  )
)
